# carcomputer_split2.net
KiCad netlist of a schematic drawn in EAGLE
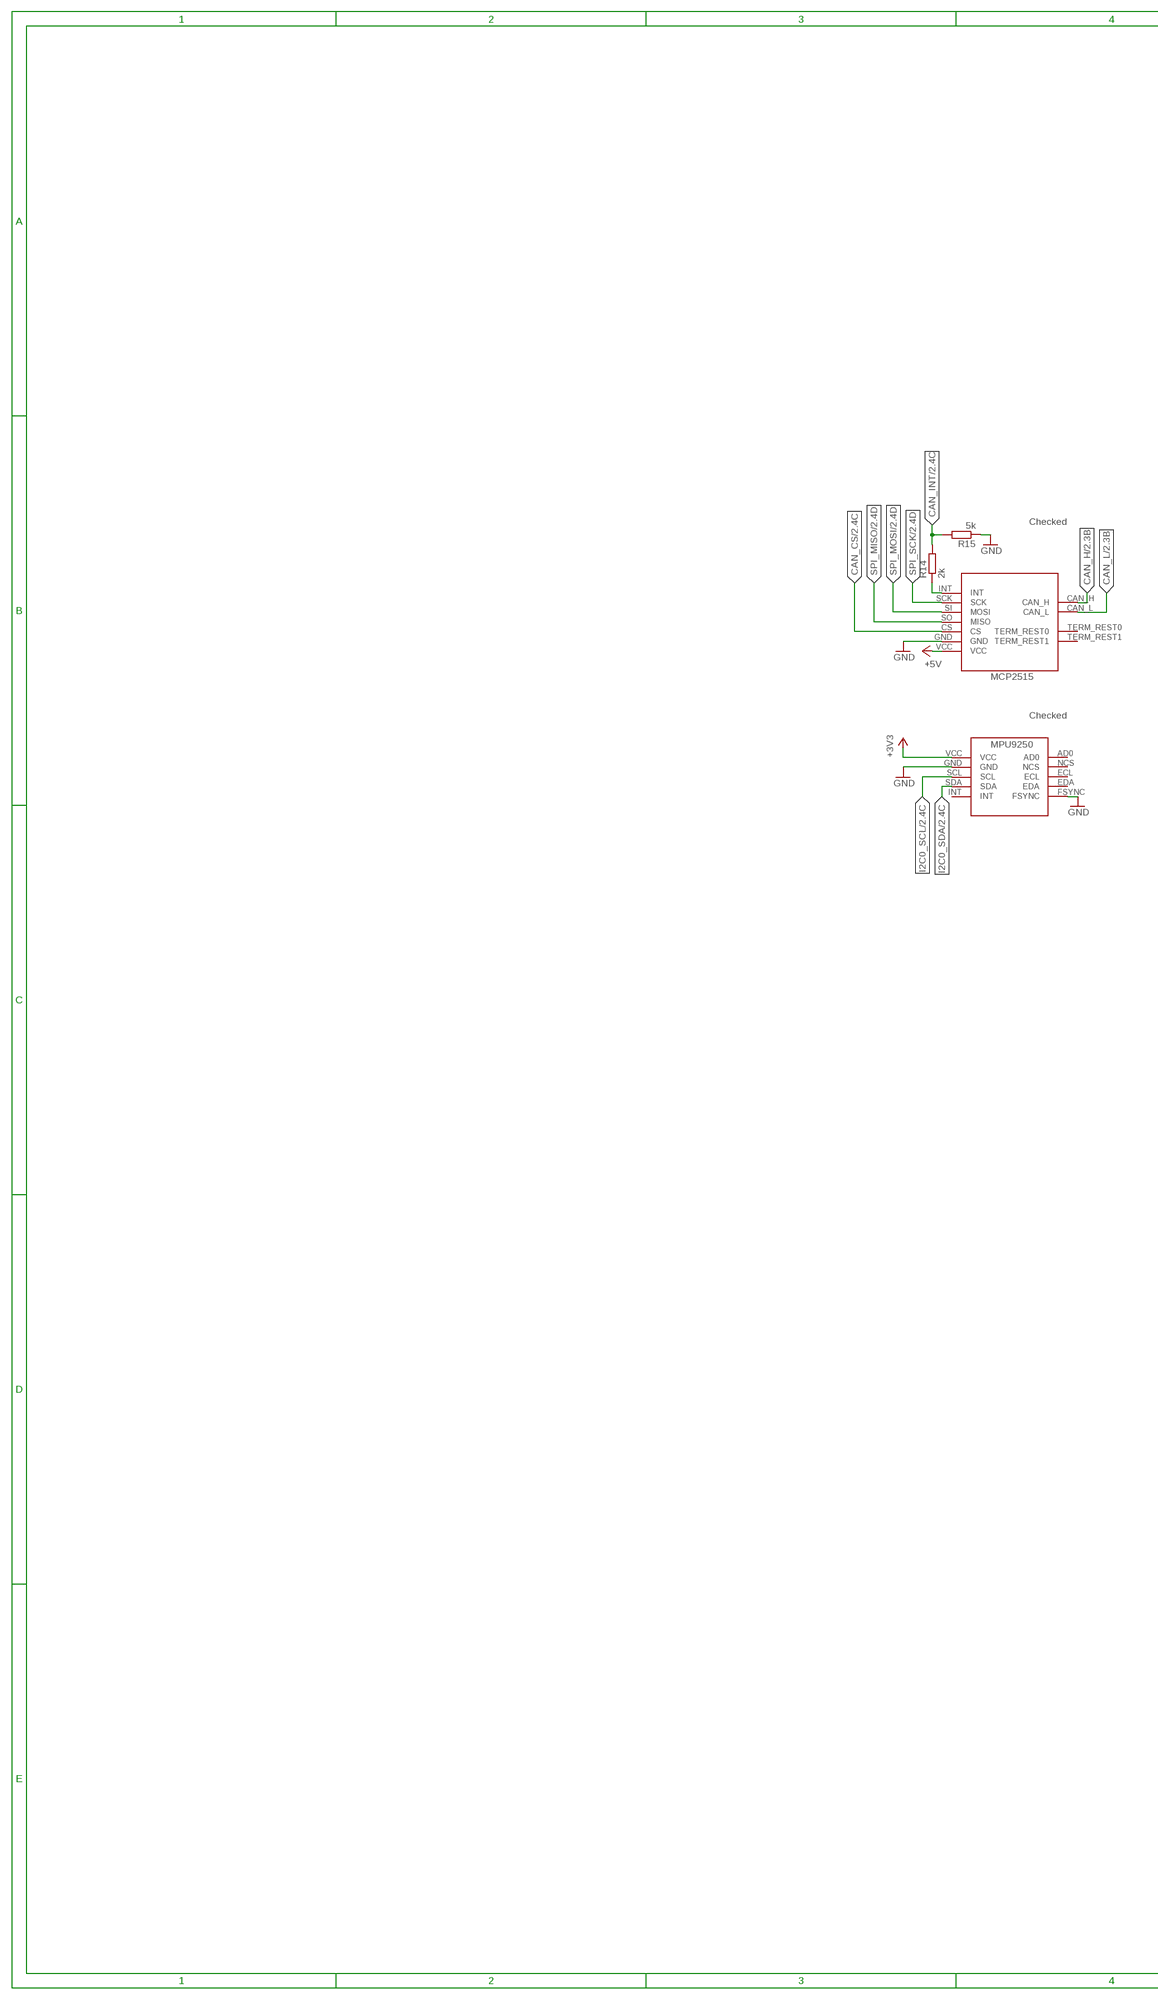
[diagram p0: schematic, sheet 1, part 1 of 2]
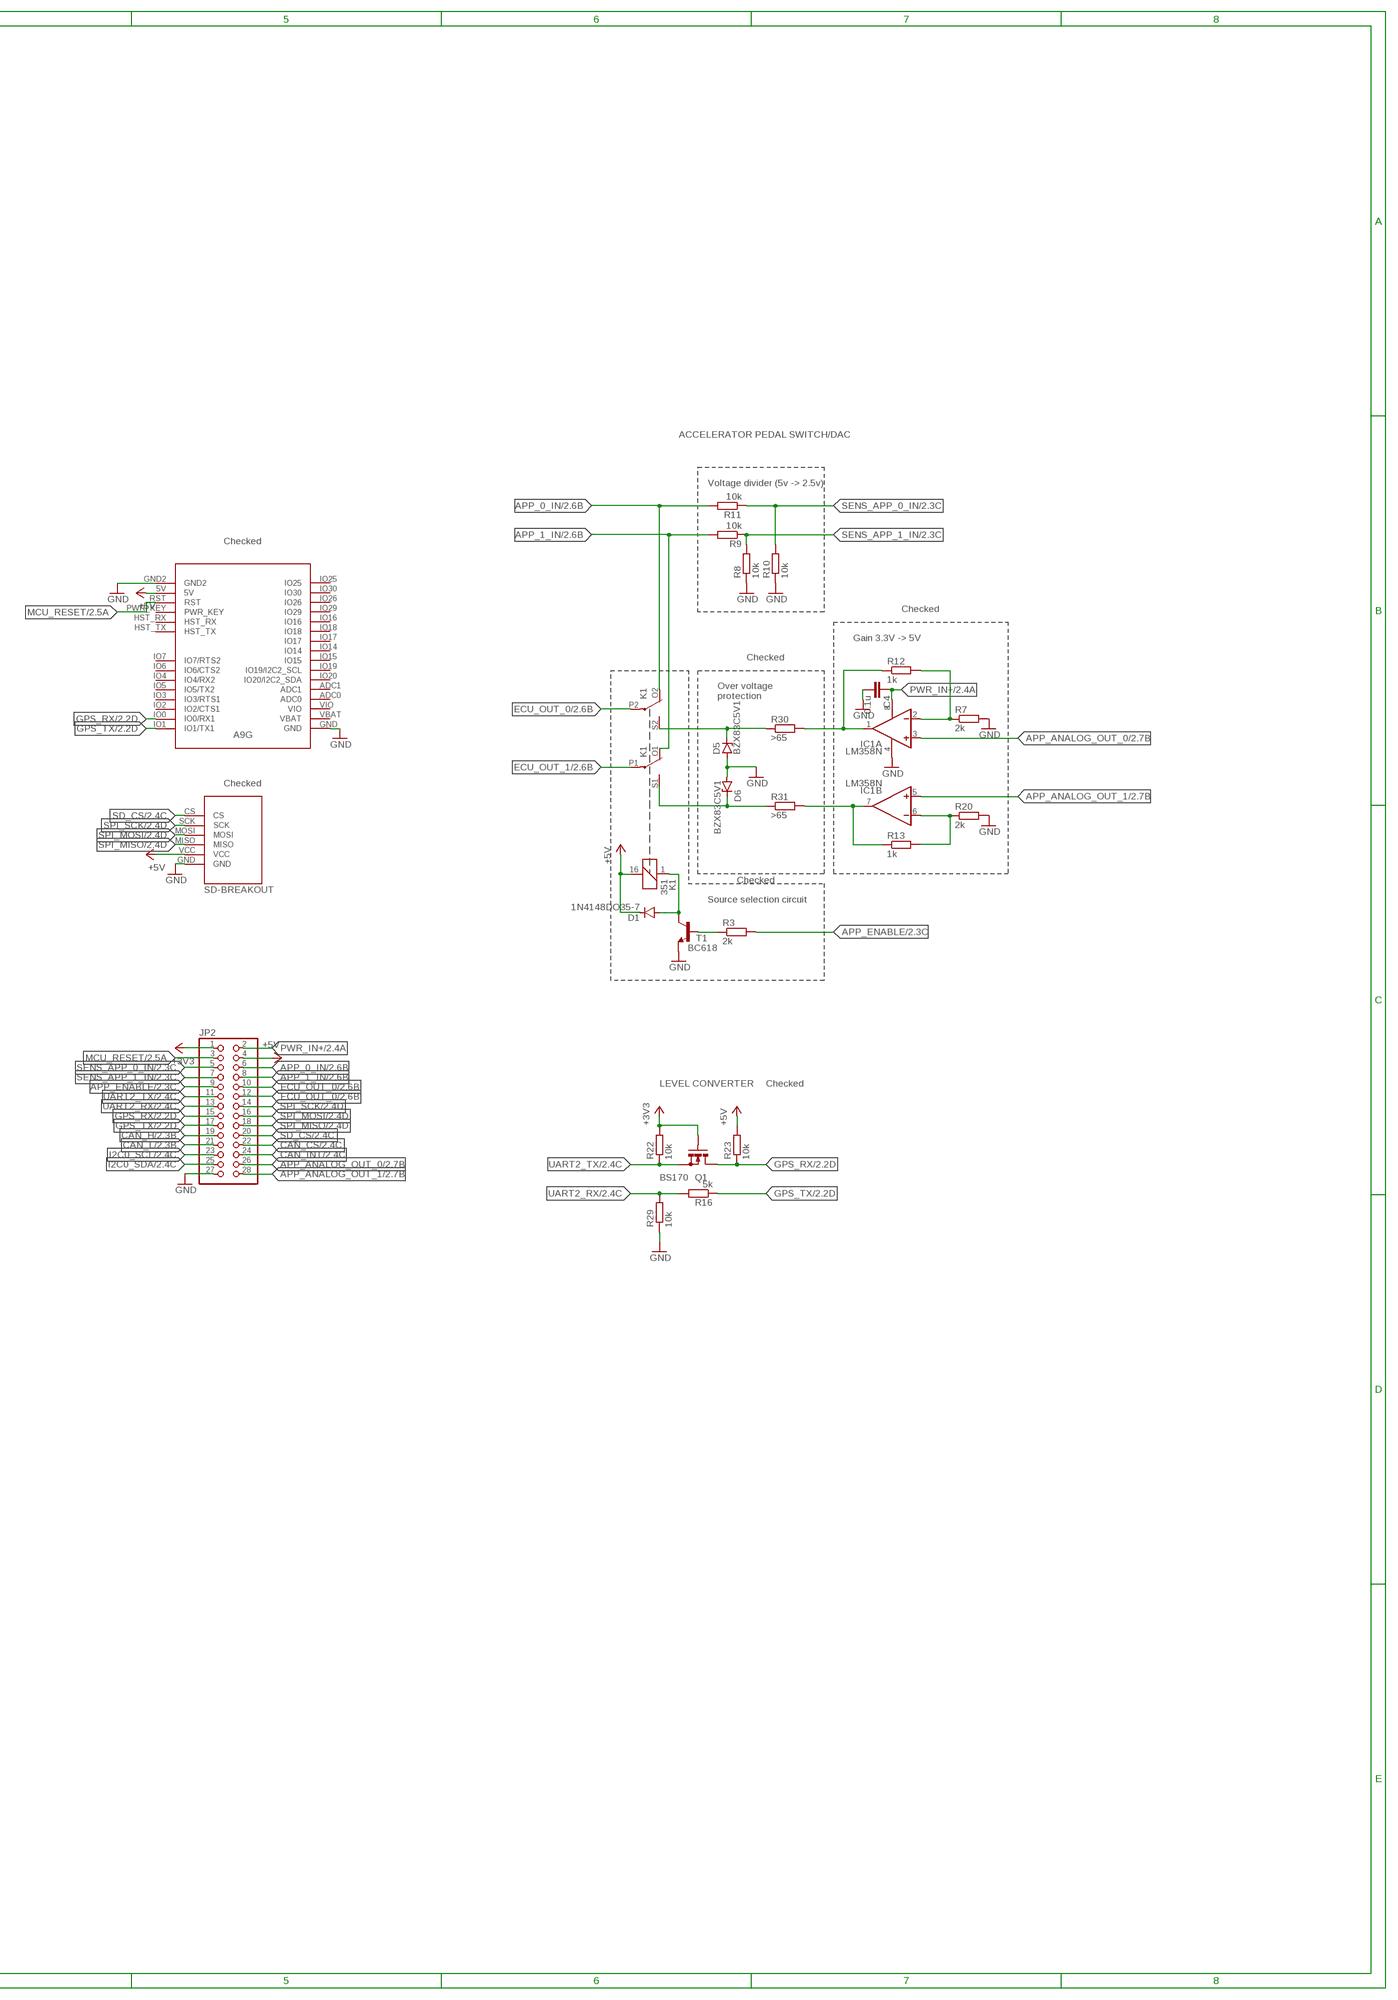
[diagram p1: schematic, sheet 1, part 2 of 2]
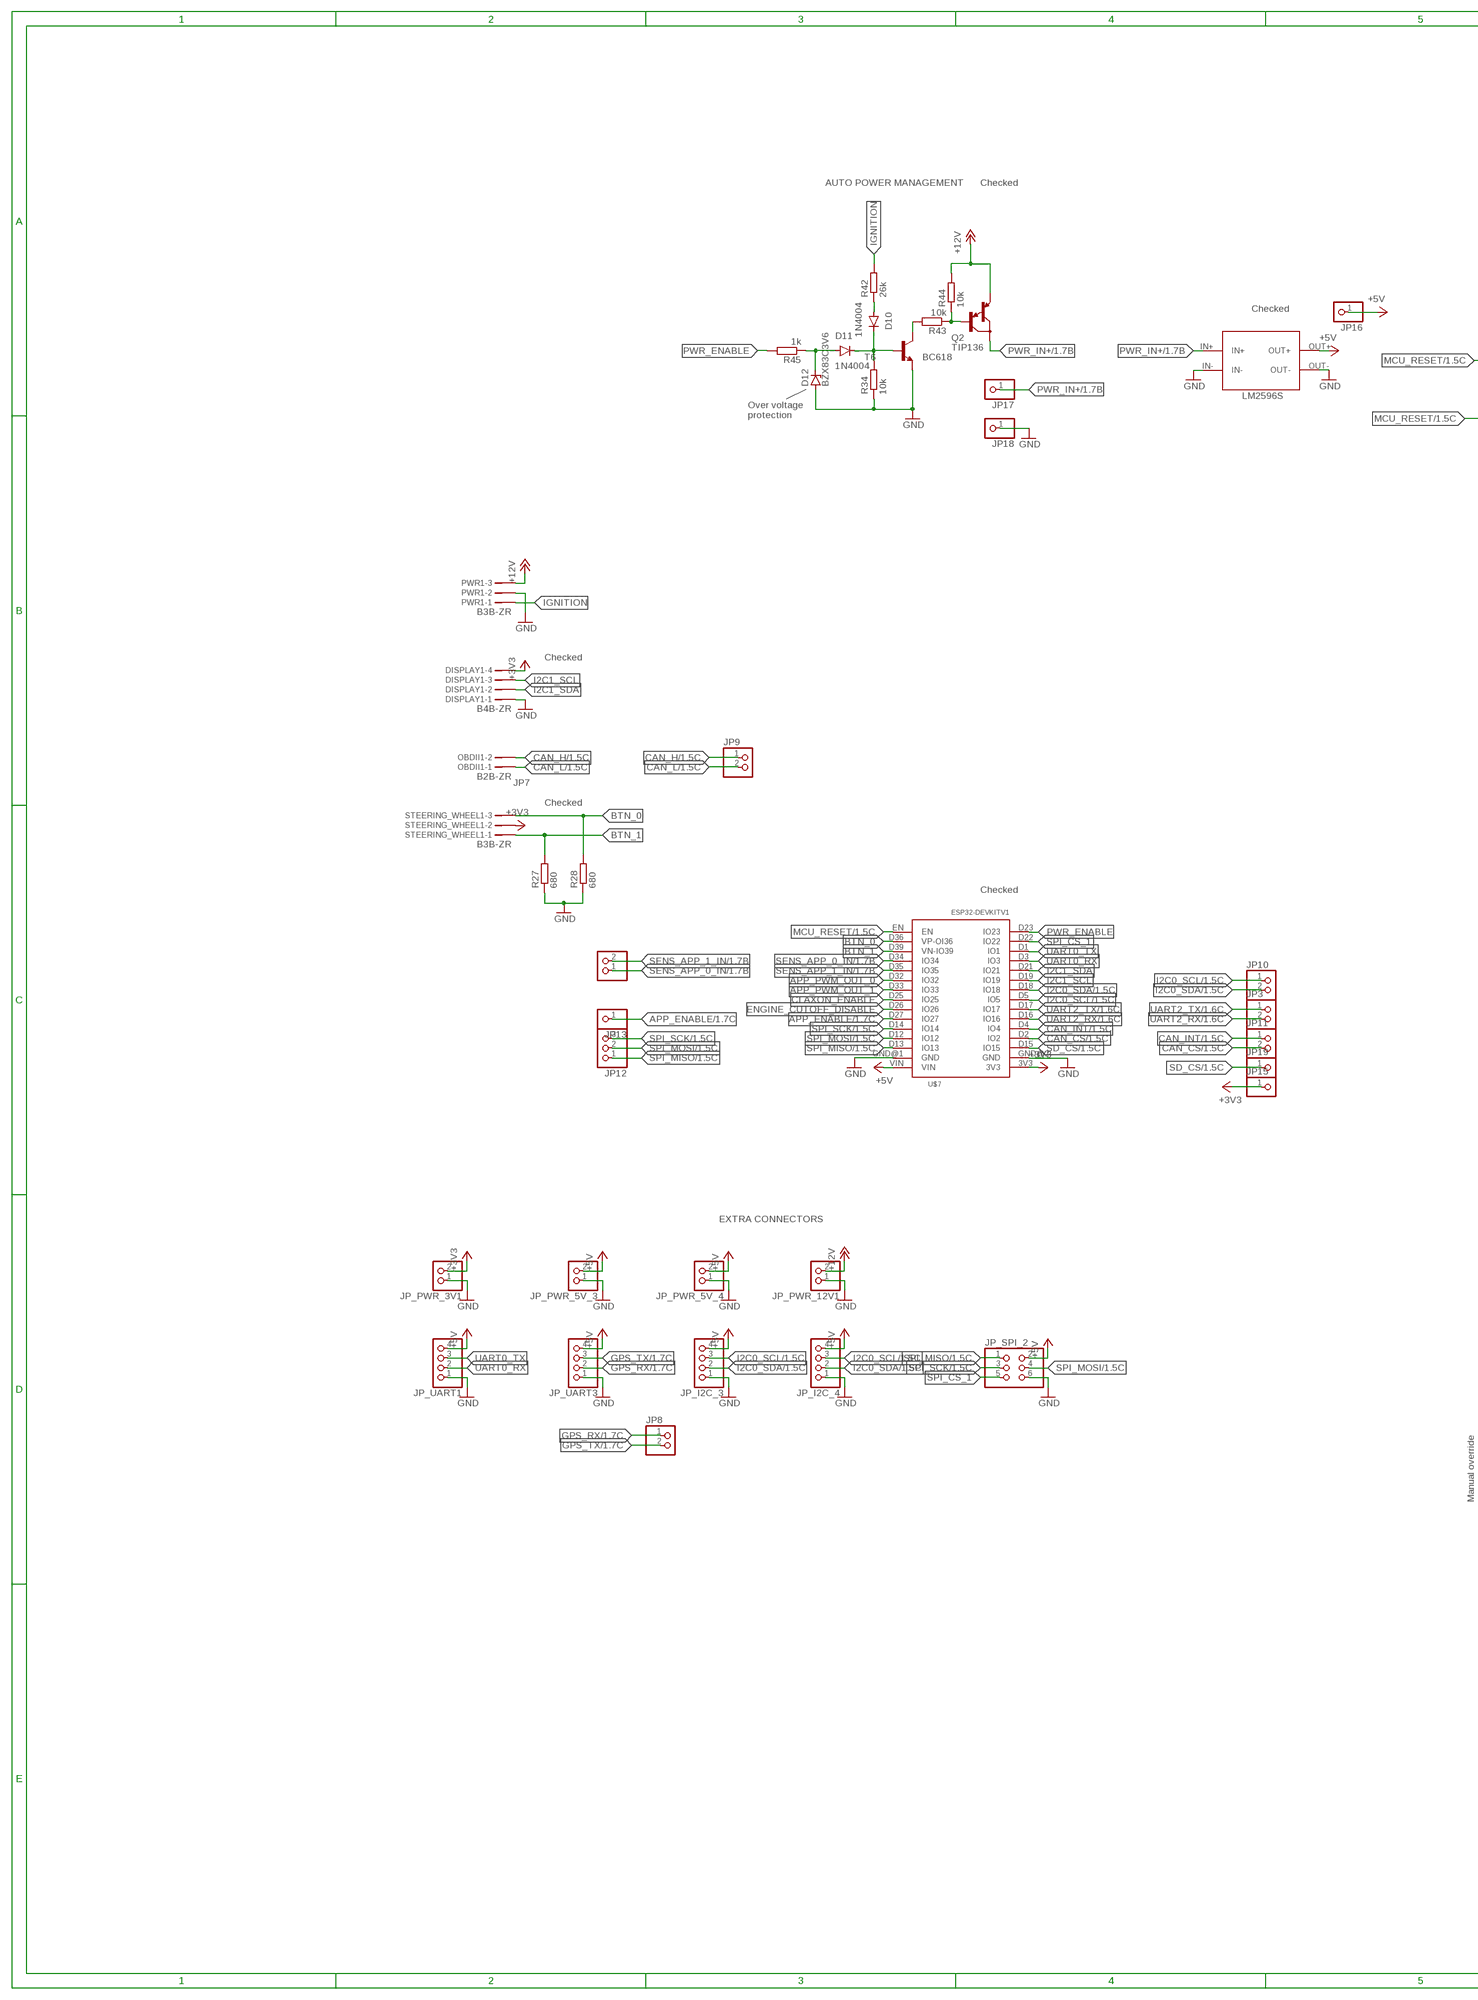
[diagram p2: schematic, sheet 2, part 1 of 2]
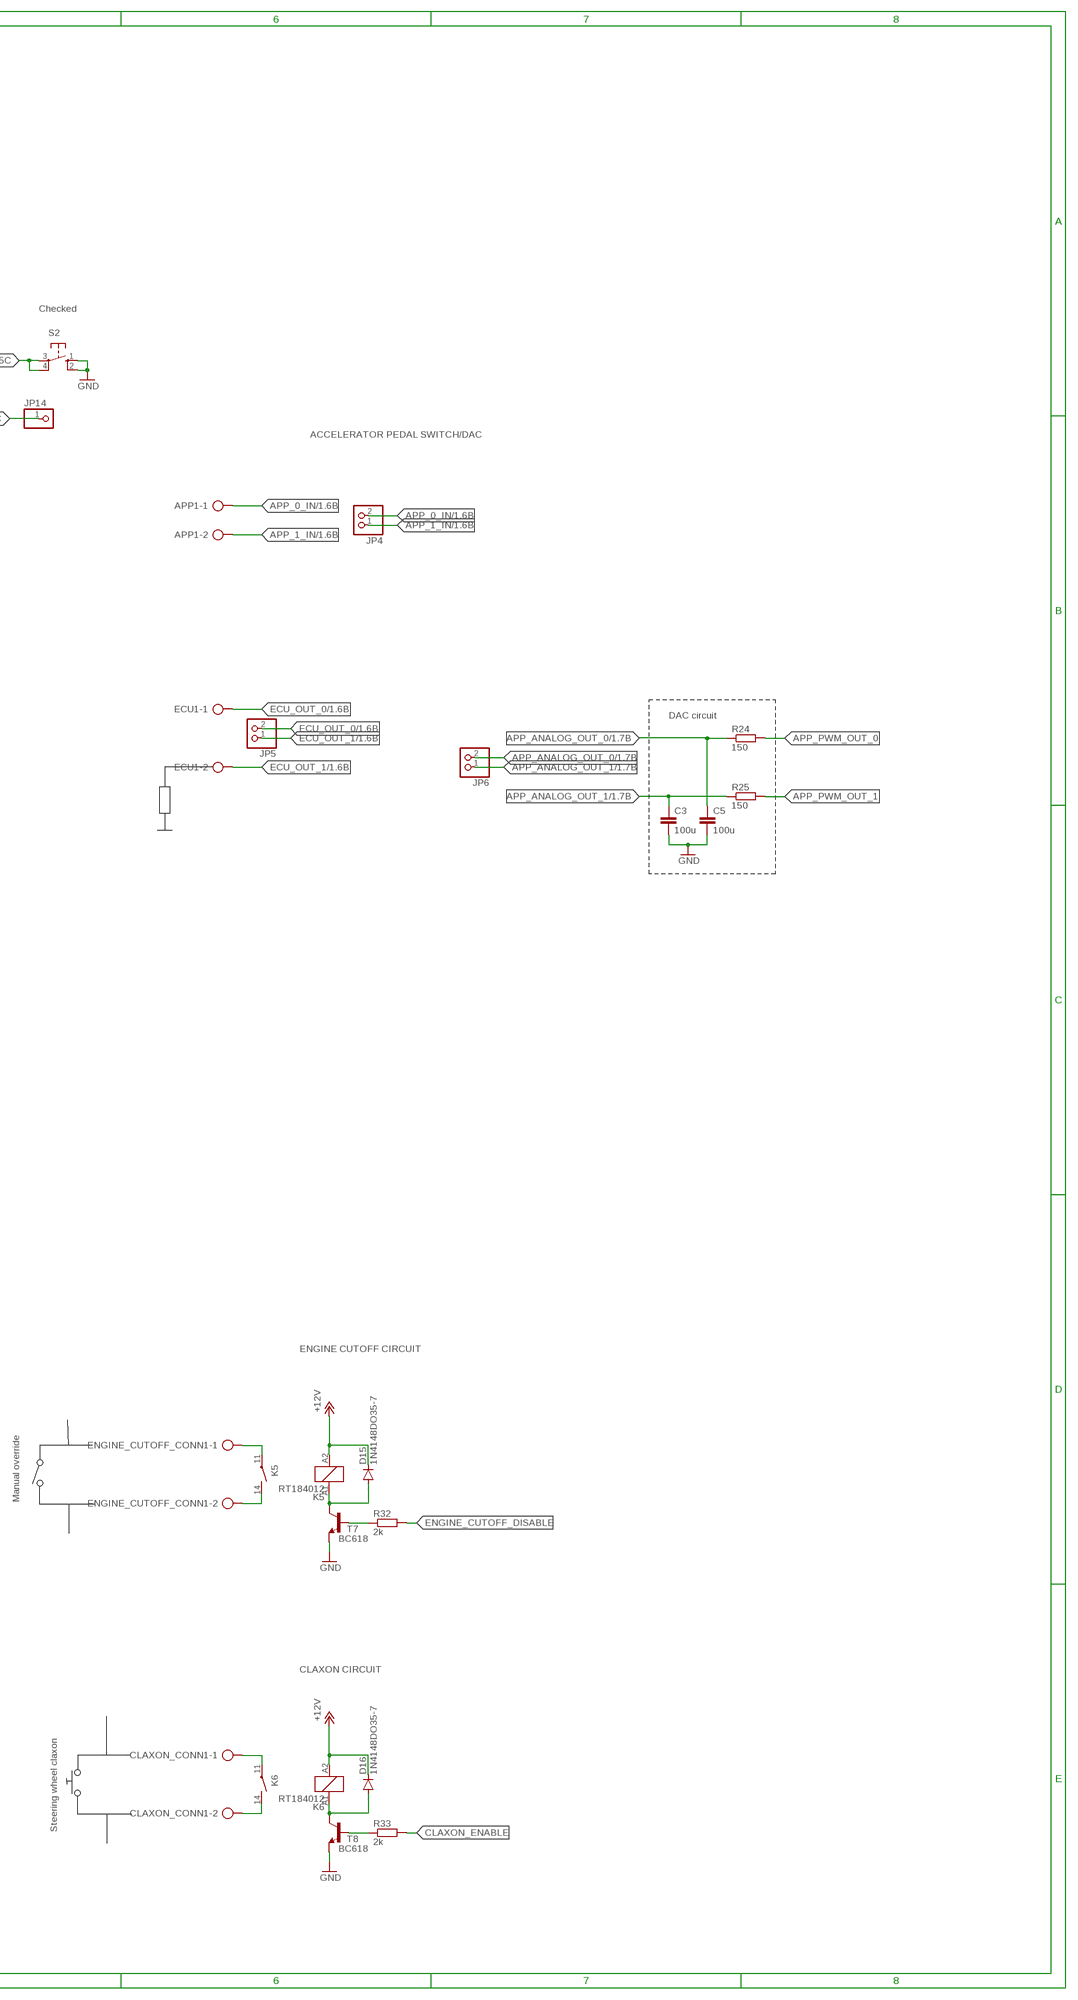
[diagram p3: schematic, sheet 2, part 2 of 2]

(export (version "E")
  (design (tool "Eeschema 10.0.6"))
  (components
    (comp (ref "APP1")
      (value "AK300/2")
      (footprint "eagle-import:AK300_2")
      (libsource (lib "eagle-import") (part "AK300/2"))
    )
    (comp (ref "C3")
      (value "100u")
      (footprint "eagle-import:C025-050X050")
      (libsource (lib "eagle-import") (part "C-EU025-050X050"))
    )
    (comp (ref "C5")
      (value "100u")
      (footprint "eagle-import:C025-050X050")
      (libsource (lib "eagle-import") (part "C-EU025-050X050"))
    )
    (comp (ref "CLAXON_CONN1")
      (value "AK300/2")
      (footprint "eagle-import:AK300_2")
      (libsource (lib "eagle-import") (part "AK300/2"))
    )
    (comp (ref "D10")
      (value "1N4004")
      (footprint "eagle-import:DO41-10")
      (libsource (lib "eagle-import") (part "1N4004"))
    )
    (comp (ref "D11")
      (value "1N4004")
      (footprint "eagle-import:DO41-10")
      (libsource (lib "eagle-import") (part "1N4004"))
    )
    (comp (ref "D12")
      (value "BZX83C3V6")
      (footprint "eagle-import:DO41Z10")
      (libsource (lib "eagle-import") (part "BZX85"))
    )
    (comp (ref "D15")
      (value "1N4148DO35-7")
      (footprint "eagle-import:DO35-7")
      (libsource (lib "eagle-import") (part "1N4148DO35-7"))
    )
    (comp (ref "D16")
      (value "1N4148DO35-7")
      (footprint "eagle-import:DO35-7")
      (libsource (lib "eagle-import") (part "1N4148DO35-7"))
    )
    (comp (ref "DISPLAY1")
      (value "B4B-ZR")
      (footprint "eagle-import:B4B-ZR")
      (fields (field (name "MF") "FARNELL") (field (name "MPN") "B4B-ZR(LF)(SN)"))
      (libsource (lib "eagle-import") (part "?4B-ZRB"))
    )
    (comp (ref "ECU1")
      (value "AK300/2")
      (footprint "eagle-import:AK300_2")
      (libsource (lib "eagle-import") (part "AK300/2"))
    )
    (comp (ref "ENGINE_CUTOFF_CONN1")
      (value "AK300/2")
      (footprint "eagle-import:AK300_2")
      (libsource (lib "eagle-import") (part "AK300/2"))
    )
    (comp (ref "JP3")
      (value "PINHD-1X2")
      (footprint "eagle-import:1X02")
      (libsource (lib "eagle-import") (part "PINHD-1X2"))
    )
    (comp (ref "JP4")
      (value "PINHD-1X2")
      (footprint "eagle-import:1X02")
      (libsource (lib "eagle-import") (part "PINHD-1X2"))
    )
    (comp (ref "JP5")
      (value "PINHD-1X2")
      (footprint "eagle-import:1X02")
      (libsource (lib "eagle-import") (part "PINHD-1X2"))
    )
    (comp (ref "JP6")
      (value "PINHD-1X2")
      (footprint "eagle-import:1X02")
      (libsource (lib "eagle-import") (part "PINHD-1X2"))
    )
    (comp (ref "JP7")
      (value "PINHD-1X2")
      (footprint "eagle-import:1X02")
      (libsource (lib "eagle-import") (part "PINHD-1X2"))
    )
    (comp (ref "JP8")
      (value "PINHD-1X2")
      (footprint "eagle-import:1X02")
      (libsource (lib "eagle-import") (part "PINHD-1X2"))
    )
    (comp (ref "JP9")
      (value "PINHD-1X2")
      (footprint "eagle-import:1X02")
      (libsource (lib "eagle-import") (part "PINHD-1X2"))
    )
    (comp (ref "JP10")
      (value "PINHD-1X2")
      (footprint "eagle-import:1X02")
      (libsource (lib "eagle-import") (part "PINHD-1X2"))
    )
    (comp (ref "JP11")
      (value "PINHD-1X2")
      (footprint "eagle-import:1X02")
      (libsource (lib "eagle-import") (part "PINHD-1X2"))
    )
    (comp (ref "JP12")
      (value "PINHD-1X3")
      (footprint "eagle-import:1X03")
      (libsource (lib "eagle-import") (part "PINHD-1X3"))
    )
    (comp (ref "JP13")
      (value "PINHD-1X1")
      (footprint "eagle-import:1X01")
      (libsource (lib "eagle-import") (part "PINHD-1X1"))
    )
    (comp (ref "JP14")
      (value "PINHD-1X1")
      (footprint "eagle-import:1X01")
      (libsource (lib "eagle-import") (part "PINHD-1X1"))
    )
    (comp (ref "JP15")
      (value "PINHD-1X1")
      (footprint "eagle-import:1X01")
      (libsource (lib "eagle-import") (part "PINHD-1X1"))
    )
    (comp (ref "JP16")
      (value "PINHD-1X1")
      (footprint "eagle-import:1X01")
      (libsource (lib "eagle-import") (part "PINHD-1X1"))
    )
    (comp (ref "JP17")
      (value "PINHD-1X1")
      (footprint "eagle-import:1X01")
      (libsource (lib "eagle-import") (part "PINHD-1X1"))
    )
    (comp (ref "JP18")
      (value "PINHD-1X1")
      (footprint "eagle-import:1X01")
      (libsource (lib "eagle-import") (part "PINHD-1X1"))
    )
    (comp (ref "JP19")
      (value "PINHD-1X1")
      (footprint "eagle-import:1X01")
      (libsource (lib "eagle-import") (part "PINHD-1X1"))
    )
    (comp (ref "JP_I2C_3")
      (value "PINHD-1X4")
      (footprint "eagle-import:1X04")
      (libsource (lib "eagle-import") (part "PINHD-1X4"))
    )
    (comp (ref "JP_I2C_4")
      (value "PINHD-1X4")
      (footprint "eagle-import:1X04")
      (libsource (lib "eagle-import") (part "PINHD-1X4"))
    )
    (comp (ref "JP_PWR_3V1")
      (value "PINHD-1X2")
      (footprint "eagle-import:1X02")
      (libsource (lib "eagle-import") (part "PINHD-1X2"))
    )
    (comp (ref "JP_PWR_5V_3")
      (value "PINHD-1X2")
      (footprint "eagle-import:1X02")
      (libsource (lib "eagle-import") (part "PINHD-1X2"))
    )
    (comp (ref "JP_PWR_5V_4")
      (value "PINHD-1X2")
      (footprint "eagle-import:1X02")
      (libsource (lib "eagle-import") (part "PINHD-1X2"))
    )
    (comp (ref "JP_PWR_12V1")
      (value "PINHD-1X2")
      (footprint "eagle-import:1X02")
      (libsource (lib "eagle-import") (part "PINHD-1X2"))
    )
    (comp (ref "JP_SPI_2")
      (value "PINHD-2X3")
      (footprint "eagle-import:2X03")
      (libsource (lib "eagle-import") (part "PINHD-2X3"))
    )
    (comp (ref "JP_UART1")
      (value "PINHD-1X4")
      (footprint "eagle-import:1X04")
      (libsource (lib "eagle-import") (part "PINHD-1X4"))
    )
    (comp (ref "JP_UART3")
      (value "PINHD-1X4")
      (footprint "eagle-import:1X04")
      (libsource (lib "eagle-import") (part "PINHD-1X4"))
    )
    (comp (ref "K5")
      (value "RT184012")
      (footprint "eagle-import:RT-N_O12A3.5")
      (fields (field (name "MF") "TYCO ELECTRONICS"))
      (libsource (lib "eagle-import") (part "RT?184012"))
    )
    (comp (ref "K6")
      (value "RT184012")
      (footprint "eagle-import:RT-N_O12A3.5")
      (fields (field (name "MF") "TYCO ELECTRONICS"))
      (libsource (lib "eagle-import") (part "RT?184012"))
    )
    (comp (ref "OBDII1")
      (value "B2B-ZR")
      (footprint "eagle-import:B2B-ZR")
      (libsource (lib "eagle-import") (part "?2B-ZRB"))
    )
    (comp (ref "PWR1")
      (value "B3B-ZR")
      (footprint "eagle-import:B3B-ZR")
      (libsource (lib "eagle-import") (part "?3B-ZRB"))
    )
    (comp (ref "Q2")
      (value "TIP136")
      (footprint "eagle-import:TO220")
      (libsource (lib "eagle-import") (part "TIP136"))
    )
    (comp (ref "R24")
      (value "150")
      (footprint "eagle-import:0207_7")
      (libsource (lib "eagle-import") (part "R-EU_0207/7"))
    )
    (comp (ref "R25")
      (value "150")
      (footprint "eagle-import:0207_7")
      (libsource (lib "eagle-import") (part "R-EU_0207/7"))
    )
    (comp (ref "R27")
      (value "680")
      (footprint "eagle-import:0207_7")
      (libsource (lib "eagle-import") (part "R-EU_0207/7"))
    )
    (comp (ref "R28")
      (value "680")
      (footprint "eagle-import:0207_7")
      (libsource (lib "eagle-import") (part "R-EU_0207/7"))
    )
    (comp (ref "R32")
      (value "2k")
      (footprint "eagle-import:0207_7")
      (libsource (lib "eagle-import") (part "R-EU_0207/7"))
    )
    (comp (ref "R33")
      (value "2k")
      (footprint "eagle-import:0207_7")
      (libsource (lib "eagle-import") (part "R-EU_0207/7"))
    )
    (comp (ref "R34")
      (value "10k")
      (footprint "eagle-import:0207_7")
      (libsource (lib "eagle-import") (part "R-EU_0207/7"))
    )
    (comp (ref "R42")
      (value "26k")
      (footprint "eagle-import:0207_7")
      (libsource (lib "eagle-import") (part "R-EU_0207/7"))
    )
    (comp (ref "R43")
      (value "10k")
      (footprint "eagle-import:0207_7")
      (libsource (lib "eagle-import") (part "R-EU_0207/7"))
    )
    (comp (ref "R44")
      (value "10k")
      (footprint "eagle-import:0207_7")
      (libsource (lib "eagle-import") (part "R-EU_0207/7"))
    )
    (comp (ref "R45")
      (value "1k")
      (footprint "eagle-import:0207_7")
      (libsource (lib "eagle-import") (part "R-EU_0207/7"))
    )
    (comp (ref "S2")
      (value "10-XX")
      (footprint "eagle-import:B3F-10XX")
      (fields (field (name "MPN") "B3F-1000"))
      (libsource (lib "eagle-import") (part "10-XX"))
    )
    (comp (ref "STEERING_WHEEL1")
      (value "B3B-ZR")
      (footprint "eagle-import:B3B-ZR")
      (libsource (lib "eagle-import") (part "?3B-ZRB"))
    )
    (comp (ref "T6")
      (value "BC618")
      (footprint "eagle-import:TO92-EBC")
      (libsource (lib "eagle-import") (part "BC618"))
    )
    (comp (ref "T7")
      (value "BC618")
      (footprint "eagle-import:TO92-EBC")
      (libsource (lib "eagle-import") (part "BC618"))
    )
    (comp (ref "T8")
      (value "BC618")
      (footprint "eagle-import:TO92-EBC")
      (libsource (lib "eagle-import") (part "BC618"))
    )
    (comp (ref "U$7")
      (value "ESP32DEVKITV1")
      (footprint "eagle-import:ESP32-DEVKITV1")
      (libsource (lib "eagle-import") (part "ESP32DEVKITV1"))
    )
    (comp (ref "U$10")
      (value "LM2596S")
      (footprint "eagle-import:LM2596S")
      (libsource (lib "eagle-import") (part "LM2596S"))
    )
    (comp (ref "C4")
      (value "0.1u")
      (footprint "eagle-import:C025-050X050")
      (libsource (lib "eagle-import") (part "C-EU025-050X050"))
    )
    (comp (ref "D1")
      (value "1N4148DO35-7")
      (footprint "eagle-import:DO35-7")
      (libsource (lib "eagle-import") (part "1N4148DO35-7"))
    )
    (comp (ref "D5")
      (value "BZX83C5V1")
      (footprint "eagle-import:DO41Z10")
      (libsource (lib "eagle-import") (part "BZX85"))
    )
    (comp (ref "D6")
      (value "BZX83C5V1")
      (footprint "eagle-import:DO41Z10")
      (libsource (lib "eagle-import") (part "BZX85"))
    )
    (comp (ref "IC1")
      (value "LM358N")
      (footprint "eagle-import:DIL08")
      (libsource (lib "eagle-import") (part "LM358N"))
    )
    (comp (ref "JP2")
      (value "PINHD-2X14")
      (footprint "eagle-import:2X14")
      (libsource (lib "eagle-import") (part "PINHD-2X14"))
    )
    (comp (ref "K1")
      (value "351")
      (footprint "eagle-import:351")
      (libsource (lib "eagle-import") (part "351"))
    )
    (comp (ref "Q1")
      (value "BS170")
      (footprint "eagle-import:SOT54E")
      (libsource (lib "eagle-import") (part "BS170"))
    )
    (comp (ref "R3")
      (value "2k")
      (footprint "eagle-import:0207_7")
      (libsource (lib "eagle-import") (part "R-EU_0207/7"))
    )
    (comp (ref "R7")
      (value "2k")
      (footprint "eagle-import:0207_7")
      (libsource (lib "eagle-import") (part "R-EU_0207/7"))
    )
    (comp (ref "R8")
      (value "10k")
      (footprint "eagle-import:0207_7")
      (libsource (lib "eagle-import") (part "R-EU_0207/7"))
    )
    (comp (ref "R9")
      (value "10k")
      (footprint "eagle-import:0207_7")
      (libsource (lib "eagle-import") (part "R-EU_0207/7"))
    )
    (comp (ref "R10")
      (value "10k")
      (footprint "eagle-import:0207_7")
      (libsource (lib "eagle-import") (part "R-EU_0207/7"))
    )
    (comp (ref "R11")
      (value "10k")
      (footprint "eagle-import:0207_7")
      (libsource (lib "eagle-import") (part "R-EU_0207/7"))
    )
    (comp (ref "R12")
      (value "1k")
      (footprint "eagle-import:0207_7")
      (libsource (lib "eagle-import") (part "R-EU_0207/7"))
    )
    (comp (ref "R13")
      (value "1k")
      (footprint "eagle-import:0207_7")
      (libsource (lib "eagle-import") (part "R-EU_0207/7"))
    )
    (comp (ref "R14")
      (value "2k")
      (footprint "eagle-import:0207_7")
      (libsource (lib "eagle-import") (part "R-EU_0207/7"))
    )
    (comp (ref "R15")
      (value "5k")
      (footprint "eagle-import:0207_7")
      (libsource (lib "eagle-import") (part "R-EU_0207/7"))
    )
    (comp (ref "R16")
      (value "5k")
      (footprint "eagle-import:0207_7")
      (libsource (lib "eagle-import") (part "R-EU_0207/7"))
    )
    (comp (ref "R20")
      (value "2k")
      (footprint "eagle-import:0207_7")
      (libsource (lib "eagle-import") (part "R-EU_0207/7"))
    )
    (comp (ref "R22")
      (value "10k")
      (footprint "eagle-import:0207_7")
      (libsource (lib "eagle-import") (part "R-EU_0207/7"))
    )
    (comp (ref "R23")
      (value "10k")
      (footprint "eagle-import:0207_7")
      (libsource (lib "eagle-import") (part "R-EU_0207/7"))
    )
    (comp (ref "R29")
      (value "10k")
      (footprint "eagle-import:0207_7")
      (libsource (lib "eagle-import") (part "R-EU_0207/7"))
    )
    (comp (ref "R30")
      (value ">65")
      (footprint "eagle-import:0207_7")
      (libsource (lib "eagle-import") (part "R-EU_0207/7"))
    )
    (comp (ref "R31")
      (value ">65")
      (footprint "eagle-import:0207_7")
      (libsource (lib "eagle-import") (part "R-EU_0207/7"))
    )
    (comp (ref "T1")
      (value "BC618")
      (footprint "eagle-import:TO92-EBC")
      (libsource (lib "eagle-import") (part "BC618"))
    )
    (comp (ref "U$2")
      (value "MCP2515_DEVBOARDINVERTED")
      (footprint "eagle-import:MCP2515_DEVBOARD_INVERTED")
      (libsource (lib "eagle-import") (part "MCP2515_DEVBOARDINVERTED"))
    )
    (comp (ref "U$3")
      (value "MPU9250_BREAKOUT")
      (footprint "eagle-import:MPU9250_BREAKOUT")
      (libsource (lib "eagle-import") (part "MPU9250_BREAKOUT"))
    )
    (comp (ref "U$5")
      (value "HKD-MICRO-SD-BREAKOUT")
      (footprint "eagle-import:HKD-MICRO-SD-BREAKOUT")
      (libsource (lib "eagle-import") (part "HKD-MICRO-SD-BREAKOUT"))
    )
    (comp (ref "U$6")
      (value "A9G")
      (footprint "eagle-import:A9G")
      (libsource (lib "eagle-import") (part "A9G"))
    )
  )
  (nets
    (net (code "1") (name "+3V3") (class "Default")
      (node (ref "DISPLAY1") (pin "4") (pinfunction "1_4") (pintype "passive"))
      (node (ref "JP15") (pin "1") (pinfunction "1_1") (pintype "passive"))
      (node (ref "JP2") (pin "1") (pinfunction "1_1") (pintype "passive"))
      (node (ref "JP_PWR_3V1") (pin "2") (pinfunction "2_2") (pintype "passive"))
      (node (ref "Q1") (pin "G") (pinfunction "G_G") (pintype "passive"))
      (node (ref "R22") (pin "2") (pinfunction "2_2") (pintype "passive"))
      (node (ref "STEERING_WHEEL1") (pin "2") (pinfunction "1_2") (pintype "passive"))
      (node (ref "U$3") (pin "VCC") (pinfunction "VCC_VCC") (pintype "bidirectional"))
      (node (ref "U$7") (pin "3V3") (pinfunction "3V3_3V3") (pintype "bidirectional"))
    )
    (net (code "2") (name "+5V") (class "Default")
      (node (ref "D1") (pin "C") (pinfunction "C_C") (pintype "passive"))
      (node (ref "JP16") (pin "1") (pinfunction "1_1") (pintype "passive"))
      (node (ref "JP2") (pin "4") (pinfunction "4_4") (pintype "passive"))
      (node (ref "JP_I2C_3") (pin "4") (pinfunction "4_4") (pintype "passive"))
      (node (ref "JP_I2C_4") (pin "4") (pinfunction "4_4") (pintype "passive"))
      (node (ref "JP_PWR_5V_3") (pin "2") (pinfunction "2_2") (pintype "passive"))
      (node (ref "JP_PWR_5V_4") (pin "2") (pinfunction "2_2") (pintype "passive"))
      (node (ref "JP_SPI_2") (pin "2") (pinfunction "2_2") (pintype "passive"))
      (node (ref "JP_UART1") (pin "4") (pinfunction "4_4") (pintype "passive"))
      (node (ref "JP_UART3") (pin "4") (pinfunction "4_4") (pintype "passive"))
      (node (ref "K1") (pin "16") (pinfunction "2_16") (pintype "passive"))
      (node (ref "R23") (pin "2") (pinfunction "2_2") (pintype "passive"))
      (node (ref "U$10") (pin "OUT+") (pinfunction "OUT+_OUT+") (pintype "bidirectional"))
      (node (ref "U$2") (pin "VCC") (pinfunction "VCC_VCC") (pintype "bidirectional"))
      (node (ref "U$5") (pin "VCC") (pinfunction "VCC_VCC") (pintype "bidirectional"))
      (node (ref "U$6") (pin "5V") (pinfunction "5V_5V") (pintype "bidirectional"))
      (node (ref "U$7") (pin "VIN") (pinfunction "VIN_VIN") (pintype "bidirectional"))
    )
    (net (code "3") (name "+12V") (class "Default")
      (node (ref "D15") (pin "C") (pinfunction "C_C") (pintype "passive"))
      (node (ref "D16") (pin "C") (pinfunction "C_C") (pintype "passive"))
      (node (ref "JP_PWR_12V1") (pin "2") (pinfunction "2_2") (pintype "passive"))
      (node (ref "K5") (pin "A2") (pinfunction "2_A2") (pintype "passive"))
      (node (ref "K6") (pin "A2") (pinfunction "2_A2") (pintype "passive"))
      (node (ref "PWR1") (pin "3") (pinfunction "1_3") (pintype "passive"))
      (node (ref "Q2") (pin "3") (pinfunction "E_3") (pintype "passive"))
      (node (ref "R44") (pin "2") (pinfunction "2_2") (pintype "passive"))
    )
    (net (code "4") (name "APP_0_IN") (class "Default")
      (node (ref "APP1") (pin "1") (pinfunction "KL_1") (pintype "passive"))
      (node (ref "JP2") (pin "6") (pinfunction "6_6") (pintype "passive"))
      (node (ref "JP4") (pin "2") (pinfunction "2_2") (pintype "passive"))
      (node (ref "K1") (pin "O2") (pinfunction "O_O2") (pintype "passive"))
      (node (ref "R11") (pin "2") (pinfunction "2_2") (pintype "passive"))
    )
    (net (code "5") (name "APP_1_IN") (class "Default")
      (node (ref "APP1") (pin "2") (pinfunction "KL_2") (pintype "passive"))
      (node (ref "JP2") (pin "8") (pinfunction "8_8") (pintype "passive"))
      (node (ref "JP4") (pin "1") (pinfunction "1_1") (pintype "passive"))
      (node (ref "K1") (pin "O1") (pinfunction "O_O1") (pintype "passive"))
      (node (ref "R9") (pin "2") (pinfunction "2_2") (pintype "passive"))
    )
    (net (code "6") (name "APP_ANALOG_OUT_0") (class "Default")
      (node (ref "C5") (pin "1") (pinfunction "1_1") (pintype "passive"))
      (node (ref "IC1") (pin "3") (pinfunction "+IN_3") (pintype "input"))
      (node (ref "JP2") (pin "26") (pinfunction "26_26") (pintype "passive"))
      (node (ref "JP6") (pin "2") (pinfunction "2_2") (pintype "passive"))
      (node (ref "R24") (pin "1") (pinfunction "1_1") (pintype "passive"))
    )
    (net (code "7") (name "APP_ANALOG_OUT_1") (class "Default")
      (node (ref "C3") (pin "1") (pinfunction "1_1") (pintype "passive"))
      (node (ref "IC1") (pin "5") (pinfunction "+IN_5") (pintype "input"))
      (node (ref "JP2") (pin "28") (pinfunction "28_28") (pintype "passive"))
      (node (ref "JP6") (pin "1") (pinfunction "1_1") (pintype "passive"))
      (node (ref "R25") (pin "1") (pinfunction "1_1") (pintype "passive"))
    )
    (net (code "8") (name "APP_ENABLE") (class "Default")
      (node (ref "JP13") (pin "1") (pinfunction "1_1") (pintype "passive"))
      (node (ref "JP2") (pin "9") (pinfunction "9_9") (pintype "passive"))
      (node (ref "R3") (pin "2") (pinfunction "2_2") (pintype "passive"))
      (node (ref "U$7") (pin "D27") (pinfunction "IO27_D27") (pintype "bidirectional"))
    )
    (net (code "9") (name "APP_PWM_OUT_0") (class "Default")
      (node (ref "R24") (pin "2") (pinfunction "2_2") (pintype "passive"))
      (node (ref "U$7") (pin "D32") (pinfunction "IO32_D32") (pintype "bidirectional"))
    )
    (net (code "10") (name "APP_PWM_OUT_1") (class "Default")
      (node (ref "R25") (pin "2") (pinfunction "2_2") (pintype "passive"))
      (node (ref "U$7") (pin "D33") (pinfunction "IO33_D33") (pintype "bidirectional"))
    )
    (net (code "11") (name "BTN_0") (class "Default")
      (node (ref "R28") (pin "2") (pinfunction "2_2") (pintype "passive"))
      (node (ref "STEERING_WHEEL1") (pin "3") (pinfunction "1_3") (pintype "passive"))
      (node (ref "U$7") (pin "D36") (pinfunction "VP-OI36_D36") (pintype "bidirectional"))
    )
    (net (code "12") (name "BTN_1") (class "Default")
      (node (ref "R27") (pin "2") (pinfunction "2_2") (pintype "passive"))
      (node (ref "STEERING_WHEEL1") (pin "1") (pinfunction "1_1") (pintype "passive"))
      (node (ref "U$7") (pin "D39") (pinfunction "VN-IO39_D39") (pintype "bidirectional"))
    )
    (net (code "13") (name "CAN_CS") (class "Default")
      (node (ref "JP11") (pin "2") (pinfunction "2_2") (pintype "passive"))
      (node (ref "JP2") (pin "22") (pinfunction "22_22") (pintype "passive"))
      (node (ref "U$2") (pin "CS") (pinfunction "CS_CS") (pintype "input"))
      (node (ref "U$7") (pin "D2") (pinfunction "IO2_D2") (pintype "bidirectional"))
    )
    (net (code "14") (name "CAN_H") (class "Default")
      (node (ref "JP2") (pin "19") (pinfunction "19_19") (pintype "passive"))
      (node (ref "JP9") (pin "1") (pinfunction "1_1") (pintype "passive"))
      (node (ref "OBDII1") (pin "2") (pinfunction "1_2") (pintype "passive"))
      (node (ref "U$2") (pin "CAN_H") (pinfunction "CAN_H_CAN_H") (pintype "bidirectional"))
    )
    (net (code "15") (name "CAN_INT") (class "Default")
      (node (ref "JP11") (pin "1") (pinfunction "1_1") (pintype "passive"))
      (node (ref "JP2") (pin "24") (pinfunction "24_24") (pintype "passive"))
      (node (ref "R14") (pin "2") (pinfunction "2_2") (pintype "passive"))
      (node (ref "R15") (pin "2") (pinfunction "2_2") (pintype "passive"))
      (node (ref "U$7") (pin "D4") (pinfunction "IO4_D4") (pintype "bidirectional"))
    )
    (net (code "16") (name "CAN_L") (class "Default")
      (node (ref "JP2") (pin "21") (pinfunction "21_21") (pintype "passive"))
      (node (ref "JP9") (pin "2") (pinfunction "2_2") (pintype "passive"))
      (node (ref "OBDII1") (pin "1") (pinfunction "1_1") (pintype "passive"))
      (node (ref "U$2") (pin "CAN_L") (pinfunction "CAN_L_CAN_L") (pintype "bidirectional"))
    )
    (net (code "17") (name "CLAXON_ENABLE") (class "Default")
      (node (ref "R33") (pin "2") (pinfunction "2_2") (pintype "passive"))
      (node (ref "U$7") (pin "D25") (pinfunction "IO25_D25") (pintype "bidirectional"))
    )
    (net (code "18") (name "ECU_OUT_0") (class "Default")
      (node (ref "ECU1") (pin "1") (pinfunction "KL_1") (pintype "passive"))
      (node (ref "JP2") (pin "10") (pinfunction "10_10") (pintype "passive"))
      (node (ref "JP2") (pin "12") (pinfunction "12_12") (pintype "passive"))
      (node (ref "JP5") (pin "2") (pinfunction "2_2") (pintype "passive"))
      (node (ref "K1") (pin "P2") (pinfunction "P_P2") (pintype "passive"))
    )
    (net (code "19") (name "ECU_OUT_1") (class "Default")
      (node (ref "ECU1") (pin "2") (pinfunction "KL_2") (pintype "passive"))
      (node (ref "JP5") (pin "1") (pinfunction "1_1") (pintype "passive"))
      (node (ref "K1") (pin "P1") (pinfunction "P_P1") (pintype "passive"))
    )
    (net (code "20") (name "ENGINE_CUTOFF_DISABLE") (class "Default")
      (node (ref "R32") (pin "2") (pinfunction "2_2") (pintype "passive"))
      (node (ref "U$7") (pin "D26") (pinfunction "IO26_D26") (pintype "bidirectional"))
    )
    (net (code "21") (name "GND") (class "Default")
      (node (ref "C3") (pin "2") (pinfunction "2_2") (pintype "passive"))
      (node (ref "C4") (pin "2") (pinfunction "2_2") (pintype "passive"))
      (node (ref "C5") (pin "2") (pinfunction "2_2") (pintype "passive"))
      (node (ref "D12") (pin "A") (pinfunction "A_A") (pintype "passive"))
      (node (ref "D5") (pin "A") (pinfunction "A_A") (pintype "passive"))
      (node (ref "D6") (pin "A") (pinfunction "A_A") (pintype "passive"))
      (node (ref "DISPLAY1") (pin "1") (pinfunction "1_1") (pintype "passive"))
      (node (ref "IC1") (pin "4") (pinfunction "V-_4") (pintype "power_in"))
      (node (ref "JP18") (pin "1") (pinfunction "1_1") (pintype "passive"))
      (node (ref "JP2") (pin "27") (pinfunction "27_27") (pintype "passive"))
      (node (ref "JP_I2C_3") (pin "1") (pinfunction "1_1") (pintype "passive"))
      (node (ref "JP_I2C_4") (pin "1") (pinfunction "1_1") (pintype "passive"))
      (node (ref "JP_PWR_12V1") (pin "1") (pinfunction "1_1") (pintype "passive"))
      (node (ref "JP_PWR_3V1") (pin "1") (pinfunction "1_1") (pintype "passive"))
      (node (ref "JP_PWR_5V_3") (pin "1") (pinfunction "1_1") (pintype "passive"))
      (node (ref "JP_PWR_5V_4") (pin "1") (pinfunction "1_1") (pintype "passive"))
      (node (ref "JP_SPI_2") (pin "6") (pinfunction "6_6") (pintype "passive"))
      (node (ref "JP_UART1") (pin "1") (pinfunction "1_1") (pintype "passive"))
      (node (ref "JP_UART3") (pin "1") (pinfunction "1_1") (pintype "passive"))
      (node (ref "PWR1") (pin "2") (pinfunction "1_2") (pintype "passive"))
      (node (ref "R10") (pin "1") (pinfunction "1_1") (pintype "passive"))
      (node (ref "R15") (pin "1") (pinfunction "1_1") (pintype "passive"))
      (node (ref "R20") (pin "2") (pinfunction "2_2") (pintype "passive"))
      (node (ref "R27") (pin "1") (pinfunction "1_1") (pintype "passive"))
      (node (ref "R28") (pin "1") (pinfunction "1_1") (pintype "passive"))
      (node (ref "R29") (pin "1") (pinfunction "1_1") (pintype "passive"))
      (node (ref "R34") (pin "1") (pinfunction "1_1") (pintype "passive"))
      (node (ref "R7") (pin "2") (pinfunction "2_2") (pintype "passive"))
      (node (ref "R8") (pin "1") (pinfunction "1_1") (pintype "passive"))
      (node (ref "S2") (pin "1") (pinfunction "S_1") (pintype "passive"))
      (node (ref "S2") (pin "2") (pinfunction "S1_2") (pintype "passive"))
      (node (ref "T1") (pin "E") (pinfunction "E_E") (pintype "passive"))
      (node (ref "T6") (pin "E") (pinfunction "E_E") (pintype "passive"))
      (node (ref "T7") (pin "E") (pinfunction "E_E") (pintype "passive"))
      (node (ref "T8") (pin "E") (pinfunction "E_E") (pintype "passive"))
      (node (ref "U$10") (pin "IN-") (pinfunction "IN-_IN-") (pintype "bidirectional"))
      (node (ref "U$10") (pin "OUT-") (pinfunction "OUT-_OUT-") (pintype "bidirectional"))
      (node (ref "U$2") (pin "GND") (pinfunction "GND_GND") (pintype "bidirectional"))
      (node (ref "U$3") (pin "FSYNC") (pinfunction "FSYNC_FSYNC") (pintype "bidirectional"))
      (node (ref "U$3") (pin "GND") (pinfunction "GND_GND") (pintype "bidirectional"))
      (node (ref "U$5") (pin "GND") (pinfunction "GND_GND") (pintype "bidirectional"))
      (node (ref "U$6") (pin "GND") (pinfunction "GND_GND") (pintype "bidirectional"))
      (node (ref "U$6") (pin "GND2") (pinfunction "GND2_GND2") (pintype "bidirectional"))
      (node (ref "U$7") (pin "GND@1") (pinfunction "GND_GND@1") (pintype "bidirectional"))
      (node (ref "U$7") (pin "GND@2") (pinfunction "GND_GND@2") (pintype "bidirectional"))
    )
    (net (code "22") (name "GPS_RX") (class "Default")
      (node (ref "JP2") (pin "15") (pinfunction "15_15") (pintype "passive"))
      (node (ref "JP8") (pin "1") (pinfunction "1_1") (pintype "passive"))
      (node (ref "JP_UART3") (pin "2") (pinfunction "2_2") (pintype "passive"))
      (node (ref "Q1") (pin "D") (pinfunction "D_D") (pintype "passive"))
      (node (ref "R23") (pin "1") (pinfunction "1_1") (pintype "passive"))
      (node (ref "U$6") (pin "IO0") (pinfunction "IO0/RX1_IO0") (pintype "bidirectional"))
    )
    (net (code "23") (name "GPS_TX") (class "Default")
      (node (ref "JP2") (pin "17") (pinfunction "17_17") (pintype "passive"))
      (node (ref "JP8") (pin "2") (pinfunction "2_2") (pintype "passive"))
      (node (ref "JP_UART3") (pin "3") (pinfunction "3_3") (pintype "passive"))
      (node (ref "R16") (pin "1") (pinfunction "1_1") (pintype "passive"))
      (node (ref "U$6") (pin "IO1") (pinfunction "IO1/TX1_IO1") (pintype "bidirectional"))
    )
    (net (code "24") (name "I2C0_SCL") (class "Default")
      (node (ref "JP10") (pin "1") (pinfunction "1_1") (pintype "passive"))
      (node (ref "JP2") (pin "23") (pinfunction "23_23") (pintype "passive"))
      (node (ref "JP_I2C_3") (pin "3") (pinfunction "3_3") (pintype "passive"))
      (node (ref "JP_I2C_4") (pin "3") (pinfunction "3_3") (pintype "passive"))
      (node (ref "U$3") (pin "SCL") (pinfunction "SCL_SCL") (pintype "bidirectional"))
      (node (ref "U$7") (pin "D5") (pinfunction "IO5_D5") (pintype "bidirectional"))
    )
    (net (code "25") (name "I2C0_SDA") (class "Default")
      (node (ref "JP10") (pin "2") (pinfunction "2_2") (pintype "passive"))
      (node (ref "JP2") (pin "25") (pinfunction "25_25") (pintype "passive"))
      (node (ref "JP_I2C_3") (pin "2") (pinfunction "2_2") (pintype "passive"))
      (node (ref "JP_I2C_4") (pin "2") (pinfunction "2_2") (pintype "passive"))
      (node (ref "U$3") (pin "SDA") (pinfunction "SDA_SDA") (pintype "bidirectional"))
      (node (ref "U$7") (pin "D18") (pinfunction "IO18_D18") (pintype "bidirectional"))
    )
    (net (code "26") (name "I2C1_SCL") (class "Default")
      (node (ref "DISPLAY1") (pin "3") (pinfunction "1_3") (pintype "passive"))
      (node (ref "U$7") (pin "D19") (pinfunction "IO19_D19") (pintype "bidirectional"))
    )
    (net (code "27") (name "I2C1_SDA") (class "Default")
      (node (ref "DISPLAY1") (pin "2") (pinfunction "1_2") (pintype "passive"))
      (node (ref "U$7") (pin "D21") (pinfunction "IO21_D21") (pintype "bidirectional"))
    )
    (net (code "28") (name "IGNITION") (class "Default")
      (node (ref "PWR1") (pin "1") (pinfunction "1_1") (pintype "passive"))
      (node (ref "R42") (pin "2") (pinfunction "2_2") (pintype "passive"))
    )
    (net (code "29") (name "MCU_RESET") (class "Default")
      (node (ref "JP14") (pin "1") (pinfunction "1_1") (pintype "passive"))
      (node (ref "JP2") (pin "3") (pinfunction "3_3") (pintype "passive"))
      (node (ref "S2") (pin "3") (pinfunction "P_3") (pintype "passive"))
      (node (ref "S2") (pin "4") (pinfunction "P1_4") (pintype "passive"))
      (node (ref "U$6") (pin "RST") (pinfunction "RST_RST") (pintype "bidirectional"))
      (node (ref "U$7") (pin "EN") (pinfunction "EN_EN") (pintype "bidirectional"))
    )
    (net (code "30") (name "Net-(CLAXON_CONN1A-KL)") (class "Default")
      (node (ref "CLAXON_CONN1") (pin "1") (pinfunction "KL_1") (pintype "passive"))
      (node (ref "K6") (pin "11") (pinfunction "P_11") (pintype "passive"))
    )
    (net (code "31") (name "Net-(CLAXON_CONN1B-KL)") (class "Default")
      (node (ref "CLAXON_CONN1") (pin "2") (pinfunction "KL_2") (pintype "passive"))
      (node (ref "K6") (pin "14") (pinfunction "S_14") (pintype "passive"))
    )
    (net (code "32") (name "Net-(D1-PadA)") (class "Default")
      (node (ref "D1") (pin "A") (pinfunction "A_A") (pintype "passive"))
      (node (ref "K1") (pin "1") (pinfunction "1_1") (pintype "passive"))
      (node (ref "T1") (pin "C") (pinfunction "C_C") (pintype "passive"))
    )
    (net (code "33") (name "Net-(D10-PadA)") (class "Default")
      (node (ref "D10") (pin "A") (pinfunction "A_A") (pintype "passive"))
      (node (ref "R42") (pin "1") (pinfunction "1_1") (pintype "passive"))
    )
    (net (code "34") (name "Net-(D10-PadC)") (class "Default")
      (node (ref "D10") (pin "C") (pinfunction "C_C") (pintype "passive"))
      (node (ref "D11") (pin "C") (pinfunction "C_C") (pintype "passive"))
      (node (ref "R34") (pin "2") (pinfunction "2_2") (pintype "passive"))
      (node (ref "T6") (pin "B") (pinfunction "B_B") (pintype "passive"))
    )
    (net (code "35") (name "Net-(D11-PadA)") (class "Default")
      (node (ref "D11") (pin "A") (pinfunction "A_A") (pintype "passive"))
      (node (ref "D12") (pin "C") (pinfunction "C_C") (pintype "passive"))
      (node (ref "R45") (pin "1") (pinfunction "1_1") (pintype "passive"))
    )
    (net (code "36") (name "Net-(ENGINE_CUTOFF_CONN1A-KL)") (class "Default")
      (node (ref "ENGINE_CUTOFF_CONN1") (pin "1") (pinfunction "KL_1") (pintype "passive"))
      (node (ref "K5") (pin "11") (pinfunction "P_11") (pintype "passive"))
    )
    (net (code "37") (name "Net-(ENGINE_CUTOFF_CONN1B-KL)") (class "Default")
      (node (ref "ENGINE_CUTOFF_CONN1") (pin "2") (pinfunction "KL_2") (pintype "passive"))
      (node (ref "K5") (pin "14") (pinfunction "S_14") (pintype "passive"))
    )
    (net (code "38") (name "Net-(IC1A--IN)") (class "Default")
      (node (ref "IC1") (pin "2") (pinfunction "-IN_2") (pintype "input"))
      (node (ref "R12") (pin "2") (pinfunction "2_2") (pintype "passive"))
      (node (ref "R7") (pin "1") (pinfunction "1_1") (pintype "passive"))
    )
    (net (code "39") (name "Net-(IC1A-OUT)") (class "Default")
      (node (ref "IC1") (pin "1") (pinfunction "OUT_1") (pintype "output"))
      (node (ref "R12") (pin "1") (pinfunction "1_1") (pintype "passive"))
      (node (ref "R30") (pin "2") (pinfunction "2_2") (pintype "passive"))
    )
    (net (code "40") (name "Net-(IC1B--IN)") (class "Default")
      (node (ref "IC1") (pin "6") (pinfunction "-IN_6") (pintype "input"))
      (node (ref "R13") (pin "2") (pinfunction "2_2") (pintype "passive"))
      (node (ref "R20") (pin "1") (pinfunction "1_1") (pintype "passive"))
    )
    (net (code "41") (name "Net-(IC1B-OUT)") (class "Default")
      (node (ref "IC1") (pin "7") (pinfunction "OUT_7") (pintype "output"))
      (node (ref "R13") (pin "1") (pinfunction "1_1") (pintype "passive"))
      (node (ref "R31") (pin "2") (pinfunction "2_2") (pintype "passive"))
    )
    (net (code "42") (name "Net-(K1B-S)") (class "Default")
      (node (ref "D6") (pin "C") (pinfunction "C_C") (pintype "passive"))
      (node (ref "K1") (pin "S1") (pinfunction "S_S1") (pintype "passive"))
      (node (ref "R31") (pin "1") (pinfunction "1_1") (pintype "passive"))
    )
    (net (code "43") (name "Net-(K1C-S)") (class "Default")
      (node (ref "D5") (pin "C") (pinfunction "C_C") (pintype "passive"))
      (node (ref "K1") (pin "S2") (pinfunction "S_S2") (pintype "passive"))
      (node (ref "R30") (pin "1") (pinfunction "1_1") (pintype "passive"))
    )
    (net (code "44") (name "Net-(K5A-1)") (class "Default")
      (node (ref "D15") (pin "A") (pinfunction "A_A") (pintype "passive"))
      (node (ref "K5") (pin "A1") (pinfunction "1_A1") (pintype "passive"))
      (node (ref "T7") (pin "C") (pinfunction "C_C") (pintype "passive"))
    )
    (net (code "45") (name "Net-(K6A-1)") (class "Default")
      (node (ref "D16") (pin "A") (pinfunction "A_A") (pintype "passive"))
      (node (ref "K6") (pin "A1") (pinfunction "1_A1") (pintype "passive"))
      (node (ref "T8") (pin "C") (pinfunction "C_C") (pintype "passive"))
    )
    (net (code "46") (name "Net-(Q2-B)") (class "Default")
      (node (ref "Q2") (pin "1") (pinfunction "B_1") (pintype "passive"))
      (node (ref "R43") (pin "1") (pinfunction "1_1") (pintype "passive"))
      (node (ref "R44") (pin "1") (pinfunction "1_1") (pintype "passive"))
    )
    (net (code "47") (name "Net-(R3-Pad1)") (class "Default")
      (node (ref "R3") (pin "1") (pinfunction "1_1") (pintype "passive"))
      (node (ref "T1") (pin "B") (pinfunction "B_B") (pintype "passive"))
    )
    (net (code "48") (name "Net-(R14-Pad1)") (class "Default")
      (node (ref "R14") (pin "1") (pinfunction "1_1") (pintype "passive"))
      (node (ref "U$2") (pin "INT") (pinfunction "INT_INT") (pintype "output"))
    )
    (net (code "49") (name "Net-(R32-Pad1)") (class "Default")
      (node (ref "R32") (pin "1") (pinfunction "1_1") (pintype "passive"))
      (node (ref "T7") (pin "B") (pinfunction "B_B") (pintype "passive"))
    )
    (net (code "50") (name "Net-(R33-Pad1)") (class "Default")
      (node (ref "R33") (pin "1") (pinfunction "1_1") (pintype "passive"))
      (node (ref "T8") (pin "B") (pinfunction "B_B") (pintype "passive"))
    )
    (net (code "51") (name "Net-(R43-Pad2)") (class "Default")
      (node (ref "R43") (pin "2") (pinfunction "2_2") (pintype "passive"))
      (node (ref "T6") (pin "C") (pinfunction "C_C") (pintype "passive"))
    )
    (net (code "52") (name "PWR_ENABLE") (class "Default")
      (node (ref "R45") (pin "2") (pinfunction "2_2") (pintype "passive"))
      (node (ref "U$7") (pin "D23") (pinfunction "IO23_D23") (pintype "bidirectional"))
    )
    (net (code "53") (name "PWR_IN+") (class "Default")
      (node (ref "C4") (pin "1") (pinfunction "1_1") (pintype "passive"))
      (node (ref "IC1") (pin "8") (pinfunction "V+_8") (pintype "power_in"))
      (node (ref "JP17") (pin "1") (pinfunction "1_1") (pintype "passive"))
      (node (ref "JP2") (pin "2") (pinfunction "2_2") (pintype "passive"))
      (node (ref "Q2") (pin "2") (pinfunction "C_2") (pintype "passive"))
      (node (ref "U$10") (pin "IN+") (pinfunction "IN+_IN+") (pintype "bidirectional"))
    )
    (net (code "54") (name "SD_CS") (class "Default")
      (node (ref "JP19") (pin "1") (pinfunction "1_1") (pintype "passive"))
      (node (ref "JP2") (pin "20") (pinfunction "20_20") (pintype "passive"))
      (node (ref "U$5") (pin "CS") (pinfunction "CS_CS") (pintype "bidirectional"))
      (node (ref "U$7") (pin "D15") (pinfunction "IO15_D15") (pintype "bidirectional"))
    )
    (net (code "55") (name "SENS_APP_0_IN") (class "Default")
      (node (ref "JP2") (pin "5") (pinfunction "5_5") (pintype "passive"))
      (node (ref "JP3") (pin "1") (pinfunction "1_1") (pintype "passive"))
      (node (ref "R10") (pin "2") (pinfunction "2_2") (pintype "passive"))
      (node (ref "R11") (pin "1") (pinfunction "1_1") (pintype "passive"))
      (node (ref "U$7") (pin "D34") (pinfunction "IO34_D34") (pintype "bidirectional"))
    )
    (net (code "56") (name "SENS_APP_1_IN") (class "Default")
      (node (ref "JP2") (pin "7") (pinfunction "7_7") (pintype "passive"))
      (node (ref "JP3") (pin "2") (pinfunction "2_2") (pintype "passive"))
      (node (ref "R8") (pin "2") (pinfunction "2_2") (pintype "passive"))
      (node (ref "R9") (pin "1") (pinfunction "1_1") (pintype "passive"))
      (node (ref "U$7") (pin "D35") (pinfunction "IO35_D35") (pintype "bidirectional"))
    )
    (net (code "57") (name "SPI_CS_1") (class "Default")
      (node (ref "JP_SPI_2") (pin "5") (pinfunction "5_5") (pintype "passive"))
      (node (ref "U$7") (pin "D22") (pinfunction "IO22_D22") (pintype "bidirectional"))
    )
    (net (code "58") (name "SPI_MISO") (class "Default")
      (node (ref "JP12") (pin "1") (pinfunction "1_1") (pintype "passive"))
      (node (ref "JP2") (pin "18") (pinfunction "18_18") (pintype "passive"))
      (node (ref "JP_SPI_2") (pin "1") (pinfunction "1_1") (pintype "passive"))
      (node (ref "U$2") (pin "SO") (pinfunction "MISO_SO") (pintype "output"))
      (node (ref "U$5") (pin "MISO") (pinfunction "MISO_MISO") (pintype "bidirectional"))
      (node (ref "U$7") (pin "D13") (pinfunction "IO13_D13") (pintype "bidirectional"))
    )
    (net (code "59") (name "SPI_MOSI") (class "Default")
      (node (ref "JP12") (pin "2") (pinfunction "2_2") (pintype "passive"))
      (node (ref "JP2") (pin "16") (pinfunction "16_16") (pintype "passive"))
      (node (ref "JP_SPI_2") (pin "4") (pinfunction "4_4") (pintype "passive"))
      (node (ref "U$2") (pin "SI") (pinfunction "MOSI_SI") (pintype "input"))
      (node (ref "U$5") (pin "MOSI") (pinfunction "MOSI_MOSI") (pintype "bidirectional"))
      (node (ref "U$7") (pin "D12") (pinfunction "IO12_D12") (pintype "bidirectional"))
    )
    (net (code "60") (name "SPI_SCK") (class "Default")
      (node (ref "JP12") (pin "3") (pinfunction "3_3") (pintype "passive"))
      (node (ref "JP2") (pin "14") (pinfunction "14_14") (pintype "passive"))
      (node (ref "JP_SPI_2") (pin "3") (pinfunction "3_3") (pintype "passive"))
      (node (ref "U$2") (pin "SCK") (pinfunction "SCK_SCK") (pintype "input"))
      (node (ref "U$5") (pin "SCK") (pinfunction "SCK_SCK") (pintype "bidirectional"))
      (node (ref "U$7") (pin "D14") (pinfunction "IO14_D14") (pintype "bidirectional"))
    )
    (net (code "61") (name "UART0_RX") (class "Default")
      (node (ref "JP_UART1") (pin "2") (pinfunction "2_2") (pintype "passive"))
      (node (ref "U$7") (pin "D3") (pinfunction "IO3_D3") (pintype "bidirectional"))
    )
    (net (code "62") (name "UART0_TX") (class "Default")
      (node (ref "JP_UART1") (pin "3") (pinfunction "3_3") (pintype "passive"))
      (node (ref "U$7") (pin "D1") (pinfunction "IO1_D1") (pintype "bidirectional"))
    )
    (net (code "63") (name "UART2_RX") (class "Default")
      (node (ref "JP2") (pin "13") (pinfunction "13_13") (pintype "passive"))
      (node (ref "JP7") (pin "2") (pinfunction "2_2") (pintype "passive"))
      (node (ref "R16") (pin "2") (pinfunction "2_2") (pintype "passive"))
      (node (ref "R29") (pin "2") (pinfunction "2_2") (pintype "passive"))
      (node (ref "U$7") (pin "D16") (pinfunction "IO16_D16") (pintype "bidirectional"))
    )
    (net (code "64") (name "UART2_TX") (class "Default")
      (node (ref "JP2") (pin "11") (pinfunction "11_11") (pintype "passive"))
      (node (ref "JP7") (pin "1") (pinfunction "1_1") (pintype "passive"))
      (node (ref "Q1") (pin "S") (pinfunction "S_S") (pintype "passive"))
      (node (ref "R22") (pin "1") (pinfunction "1_1") (pintype "passive"))
      (node (ref "U$7") (pin "D17") (pinfunction "IO17_D17") (pintype "bidirectional"))
    )
    (net (code "65") (name "unconnected-(U$2-PadTERM_REST0)") (class "Default")
      (node (ref "U$2") (pin "TERM_REST0") (pinfunction "TERM_REST0_TERM_REST0") (pintype "bidirectional"))
    )
    (net (code "66") (name "unconnected-(U$2-PadTERM_REST1)") (class "Default")
      (node (ref "U$2") (pin "TERM_REST1") (pinfunction "TERM_REST1_TERM_REST1") (pintype "bidirectional"))
    )
    (net (code "67") (name "unconnected-(U$3-PadAD0)") (class "Default")
      (node (ref "U$3") (pin "AD0") (pinfunction "AD0_AD0") (pintype "bidirectional"))
    )
    (net (code "68") (name "unconnected-(U$3-PadECL)") (class "Default")
      (node (ref "U$3") (pin "ECL") (pinfunction "ECL_ECL") (pintype "bidirectional"))
    )
    (net (code "69") (name "unconnected-(U$3-PadEDA)") (class "Default")
      (node (ref "U$3") (pin "EDA") (pinfunction "EDA_EDA") (pintype "bidirectional"))
    )
    (net (code "70") (name "unconnected-(U$3-PadINT)") (class "Default")
      (node (ref "U$3") (pin "INT") (pinfunction "INT_INT") (pintype "bidirectional"))
    )
    (net (code "71") (name "unconnected-(U$3-PadNCS)") (class "Default")
      (node (ref "U$3") (pin "NCS") (pinfunction "NCS_NCS") (pintype "bidirectional"))
    )
    (net (code "72") (name "unconnected-(U$6-IO2{slash}CTS1-PadIO2)") (class "Default")
      (node (ref "U$6") (pin "IO2") (pinfunction "IO2/CTS1_IO2") (pintype "bidirectional"))
    )
    (net (code "73") (name "unconnected-(U$6-IO3{slash}RTS1-PadIO3)") (class "Default")
      (node (ref "U$6") (pin "IO3") (pinfunction "IO3/RTS1_IO3") (pintype "bidirectional"))
    )
    (net (code "74") (name "unconnected-(U$6-IO4{slash}RX2-PadIO4)") (class "Default")
      (node (ref "U$6") (pin "IO4") (pinfunction "IO4/RX2_IO4") (pintype "bidirectional"))
    )
    (net (code "75") (name "unconnected-(U$6-IO5{slash}TX2-PadIO5)") (class "Default")
      (node (ref "U$6") (pin "IO5") (pinfunction "IO5/TX2_IO5") (pintype "bidirectional"))
    )
    (net (code "76") (name "unconnected-(U$6-IO6{slash}CTS2-PadIO6)") (class "Default")
      (node (ref "U$6") (pin "IO6") (pinfunction "IO6/CTS2_IO6") (pintype "bidirectional"))
    )
    (net (code "77") (name "unconnected-(U$6-IO7{slash}RTS2-PadIO7)") (class "Default")
      (node (ref "U$6") (pin "IO7") (pinfunction "IO7/RTS2_IO7") (pintype "bidirectional"))
    )
    (net (code "78") (name "unconnected-(U$6-IO19{slash}I2C2_SCL-PadIO19)") (class "Default")
      (node (ref "U$6") (pin "IO19") (pinfunction "IO19/I2C2_SCL_IO19") (pintype "bidirectional"))
    )
    (net (code "79") (name "unconnected-(U$6-IO20{slash}I2C2_SDA-PadIO20)") (class "Default")
      (node (ref "U$6") (pin "IO20") (pinfunction "IO20/I2C2_SDA_IO20") (pintype "bidirectional"))
    )
    (net (code "80") (name "unconnected-(U$6-PadADC0)") (class "Default")
      (node (ref "U$6") (pin "ADC0") (pinfunction "ADC0_ADC0") (pintype "bidirectional"))
    )
    (net (code "81") (name "unconnected-(U$6-PadADC1)") (class "Default")
      (node (ref "U$6") (pin "ADC1") (pinfunction "ADC1_ADC1") (pintype "bidirectional"))
    )
    (net (code "82") (name "unconnected-(U$6-PadHST_RX)") (class "Default")
      (node (ref "U$6") (pin "HST_RX") (pinfunction "HST_RX_HST_RX") (pintype "bidirectional"))
    )
    (net (code "83") (name "unconnected-(U$6-PadHST_TX)") (class "Default")
      (node (ref "U$6") (pin "HST_TX") (pinfunction "HST_TX_HST_TX") (pintype "bidirectional"))
    )
    (net (code "84") (name "unconnected-(U$6-PadIO14)") (class "Default")
      (node (ref "U$6") (pin "IO14") (pinfunction "IO14_IO14") (pintype "bidirectional"))
    )
    (net (code "85") (name "unconnected-(U$6-PadIO15)") (class "Default")
      (node (ref "U$6") (pin "IO15") (pinfunction "IO15_IO15") (pintype "bidirectional"))
    )
    (net (code "86") (name "unconnected-(U$6-PadIO16)") (class "Default")
      (node (ref "U$6") (pin "IO16") (pinfunction "IO16_IO16") (pintype "bidirectional"))
    )
    (net (code "87") (name "unconnected-(U$6-PadIO17)") (class "Default")
      (node (ref "U$6") (pin "IO17") (pinfunction "IO17_IO17") (pintype "bidirectional"))
    )
    (net (code "88") (name "unconnected-(U$6-PadIO18)") (class "Default")
      (node (ref "U$6") (pin "IO18") (pinfunction "IO18_IO18") (pintype "bidirectional"))
    )
    (net (code "89") (name "unconnected-(U$6-PadIO25)") (class "Default")
      (node (ref "U$6") (pin "IO25") (pinfunction "IO25_IO25") (pintype "bidirectional"))
    )
    (net (code "90") (name "unconnected-(U$6-PadIO26)") (class "Default")
      (node (ref "U$6") (pin "IO26") (pinfunction "IO26_IO26") (pintype "bidirectional"))
    )
    (net (code "91") (name "unconnected-(U$6-PadIO29)") (class "Default")
      (node (ref "U$6") (pin "IO29") (pinfunction "IO29_IO29") (pintype "bidirectional"))
    )
    (net (code "92") (name "unconnected-(U$6-PadIO30)") (class "Default")
      (node (ref "U$6") (pin "IO30") (pinfunction "IO30_IO30") (pintype "bidirectional"))
    )
    (net (code "93") (name "unconnected-(U$6-PadPWR_KEY)") (class "Default")
      (node (ref "U$6") (pin "PWR_KEY") (pinfunction "PWR_KEY_PWR_KEY") (pintype "bidirectional"))
    )
    (net (code "94") (name "unconnected-(U$6-PadVBAT)") (class "Default")
      (node (ref "U$6") (pin "VBAT") (pinfunction "VBAT_VBAT") (pintype "bidirectional"))
    )
    (net (code "95") (name "unconnected-(U$6-PadVIO)") (class "Default")
      (node (ref "U$6") (pin "VIO") (pinfunction "VIO_VIO") (pintype "bidirectional"))
    )
  )
)
